# PCIE_USB.net
KiCad netlist of a schematic drawn in Altium Designer
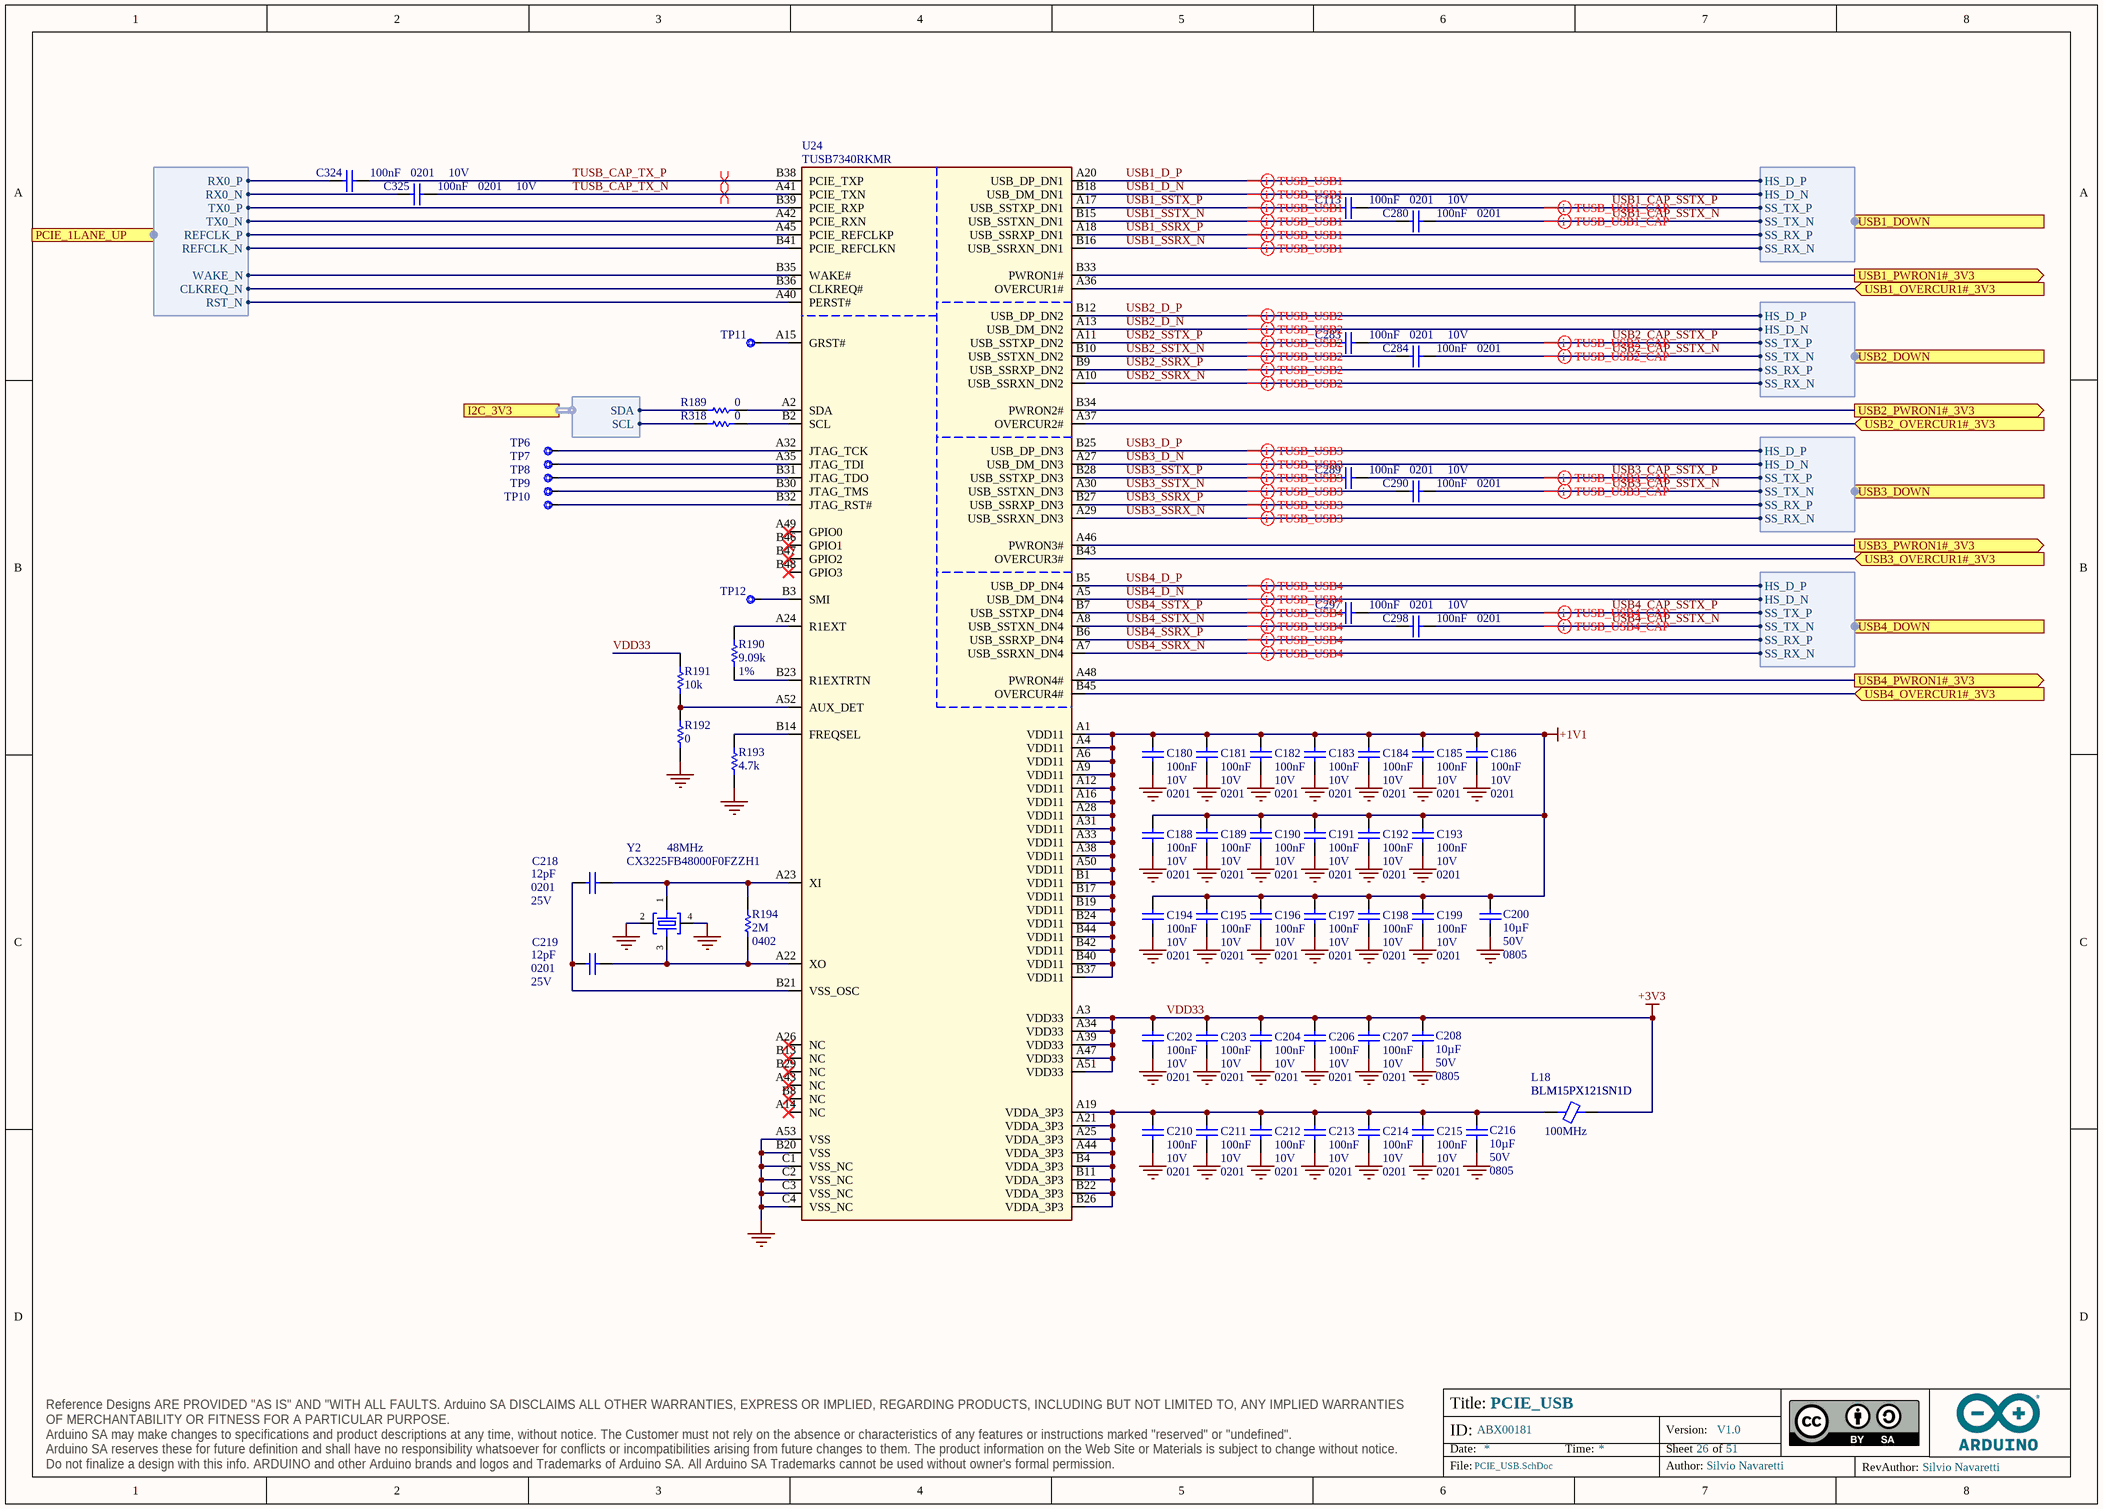
[diagram p0: PCIE_USB.SchDoc]

(export (version "E")
  (design (tool "Eeschema 10.0.6"))
  (components
    (comp (ref "C113")
      (value "100nF")
      (footprint "CAP-0201")
      (description "CAP CHIP 0201 100nF 10% 10V X5R")
      (fields
        (field (name "CASE CODE (IMPERIAL)") "0201")
        (field (name "TOLERANCE") "10%")
        (field (name "PART NUMBER") "CL03A104KP3NNNC")
        (field (name "VOLTAGE") "10V")
      )
      (libsource (lib "Clean") (part "CAP"))
    )
    (comp (ref "C180")
      (value "100nF")
      (footprint "CAP-0201")
      (description "CAP CHIP 0201 100nF 10% 10V X5R")
      (fields
        (field (name "PART NUMBER") "CL03A104KP3NNNC")
        (field (name "MANUFACTURER") "Samsung Electro-Mechanics")
        (field (name "VOLTAGE") "10V")
        (field (name "CASE CODE (IMPERIAL)") "0201")
      )
      (libsource (lib "Clean") (part "CAP"))
    )
    (comp (ref "C181")
      (value "100nF")
      (footprint "CAP-0201")
      (description "CAP CHIP 0201 100nF 10% 10V X5R")
      (fields
        (field (name "PART NUMBER") "CL03A104KP3NNNC")
        (field (name "MANUFACTURER") "Samsung Electro-Mechanics")
        (field (name "VOLTAGE") "10V")
        (field (name "CASE CODE (IMPERIAL)") "0201")
      )
      (libsource (lib "Clean") (part "CAP"))
    )
    (comp (ref "C182")
      (value "100nF")
      (footprint "CAP-0201")
      (description "CAP CHIP 0201 100nF 10% 10V X5R")
      (fields
        (field (name "PART NUMBER") "CL03A104KP3NNNC")
        (field (name "MANUFACTURER") "Samsung Electro-Mechanics")
        (field (name "VOLTAGE") "10V")
        (field (name "CASE CODE (IMPERIAL)") "0201")
      )
      (libsource (lib "Clean") (part "CAP"))
    )
    (comp (ref "C183")
      (value "100nF")
      (footprint "CAP-0201")
      (description "CAP CHIP 0201 100nF 10% 10V X5R")
      (fields
        (field (name "PART NUMBER") "CL03A104KP3NNNC")
        (field (name "MANUFACTURER") "Samsung Electro-Mechanics")
        (field (name "VOLTAGE") "10V")
        (field (name "CASE CODE (IMPERIAL)") "0201")
      )
      (libsource (lib "Clean") (part "CAP"))
    )
    (comp (ref "C184")
      (value "100nF")
      (footprint "CAP-0201")
      (description "CAP CHIP 0201 100nF 10% 10V X5R")
      (fields
        (field (name "PART NUMBER") "CL03A104KP3NNNC")
        (field (name "MANUFACTURER") "Samsung Electro-Mechanics")
        (field (name "VOLTAGE") "10V")
        (field (name "CASE CODE (IMPERIAL)") "0201")
      )
      (libsource (lib "Clean") (part "CAP"))
    )
    (comp (ref "C185")
      (value "100nF")
      (footprint "CAP-0201")
      (description "CAP CHIP 0201 100nF 10% 10V X5R")
      (fields
        (field (name "PART NUMBER") "CL03A104KP3NNNC")
        (field (name "MANUFACTURER") "Samsung Electro-Mechanics")
        (field (name "VOLTAGE") "10V")
        (field (name "CASE CODE (IMPERIAL)") "0201")
      )
      (libsource (lib "Clean") (part "CAP"))
    )
    (comp (ref "C186")
      (value "100nF")
      (footprint "CAP-0201")
      (description "CAP CHIP 0201 100nF 10% 10V X5R")
      (fields
        (field (name "PART NUMBER") "CL03A104KP3NNNC")
        (field (name "MANUFACTURER") "Samsung Electro-Mechanics")
        (field (name "VOLTAGE") "10V")
        (field (name "CASE CODE (IMPERIAL)") "0201")
      )
      (libsource (lib "Clean") (part "CAP"))
    )
    (comp (ref "C188")
      (value "100nF")
      (footprint "CAP-0201")
      (description "CAP CHIP 0201 100nF 10% 10V X5R")
      (fields
        (field (name "PART NUMBER") "CL03A104KP3NNNC")
        (field (name "MANUFACTURER") "Samsung Electro-Mechanics")
        (field (name "VOLTAGE") "10V")
        (field (name "CASE CODE (IMPERIAL)") "0201")
      )
      (libsource (lib "Clean") (part "CAP"))
    )
    (comp (ref "C189")
      (value "100nF")
      (footprint "CAP-0201")
      (description "CAP CHIP 0201 100nF 10% 10V X5R")
      (fields
        (field (name "PART NUMBER") "CL03A104KP3NNNC")
        (field (name "MANUFACTURER") "Samsung Electro-Mechanics")
        (field (name "VOLTAGE") "10V")
        (field (name "CASE CODE (IMPERIAL)") "0201")
      )
      (libsource (lib "Clean") (part "CAP"))
    )
    (comp (ref "C190")
      (value "100nF")
      (footprint "CAP-0201")
      (description "CAP CHIP 0201 100nF 10% 10V X5R")
      (fields
        (field (name "PART NUMBER") "CL03A104KP3NNNC")
        (field (name "MANUFACTURER") "Samsung Electro-Mechanics")
        (field (name "VOLTAGE") "10V")
        (field (name "CASE CODE (IMPERIAL)") "0201")
      )
      (libsource (lib "Clean") (part "CAP"))
    )
    (comp (ref "C191")
      (value "100nF")
      (footprint "CAP-0201")
      (description "CAP CHIP 0201 100nF 10% 10V X5R")
      (fields
        (field (name "PART NUMBER") "CL03A104KP3NNNC")
        (field (name "MANUFACTURER") "Samsung Electro-Mechanics")
        (field (name "VOLTAGE") "10V")
        (field (name "CASE CODE (IMPERIAL)") "0201")
      )
      (libsource (lib "Clean") (part "CAP"))
    )
    (comp (ref "C192")
      (value "100nF")
      (footprint "CAP-0201")
      (description "CAP CHIP 0201 100nF 10% 10V X5R")
      (fields
        (field (name "PART NUMBER") "CL03A104KP3NNNC")
        (field (name "MANUFACTURER") "Samsung Electro-Mechanics")
        (field (name "VOLTAGE") "10V")
        (field (name "CASE CODE (IMPERIAL)") "0201")
      )
      (libsource (lib "Clean") (part "CAP"))
    )
    (comp (ref "C193")
      (value "100nF")
      (footprint "CAP-0201")
      (description "CAP CHIP 0201 100nF 10% 10V X5R")
      (fields
        (field (name "PART NUMBER") "CL03A104KP3NNNC")
        (field (name "MANUFACTURER") "Samsung Electro-Mechanics")
        (field (name "VOLTAGE") "10V")
        (field (name "CASE CODE (IMPERIAL)") "0201")
      )
      (libsource (lib "Clean") (part "CAP"))
    )
    (comp (ref "C194")
      (value "100nF")
      (footprint "CAP-0201")
      (description "CAP CHIP 0201 100nF 10% 10V X5R")
      (fields
        (field (name "PART NUMBER") "CL03A104KP3NNNC")
        (field (name "MANUFACTURER") "Samsung Electro-Mechanics")
        (field (name "VOLTAGE") "10V")
        (field (name "CASE CODE (IMPERIAL)") "0201")
      )
      (libsource (lib "Clean") (part "CAP"))
    )
    (comp (ref "C195")
      (value "100nF")
      (footprint "CAP-0201")
      (description "CAP CHIP 0201 100nF 10% 10V X5R")
      (fields
        (field (name "PART NUMBER") "CL03A104KP3NNNC")
        (field (name "MANUFACTURER") "Samsung Electro-Mechanics")
        (field (name "VOLTAGE") "10V")
        (field (name "CASE CODE (IMPERIAL)") "0201")
      )
      (libsource (lib "Clean") (part "CAP"))
    )
    (comp (ref "C196")
      (value "100nF")
      (footprint "CAP-0201")
      (description "CAP CHIP 0201 100nF 10% 10V X5R")
      (fields
        (field (name "PART NUMBER") "CL03A104KP3NNNC")
        (field (name "MANUFACTURER") "Samsung Electro-Mechanics")
        (field (name "VOLTAGE") "10V")
        (field (name "CASE CODE (IMPERIAL)") "0201")
      )
      (libsource (lib "Clean") (part "CAP"))
    )
    (comp (ref "C197")
      (value "100nF")
      (footprint "CAP-0201")
      (description "CAP CHIP 0201 100nF 10% 10V X5R")
      (fields
        (field (name "PART NUMBER") "CL03A104KP3NNNC")
        (field (name "MANUFACTURER") "Samsung Electro-Mechanics")
        (field (name "VOLTAGE") "10V")
        (field (name "CASE CODE (IMPERIAL)") "0201")
      )
      (libsource (lib "Clean") (part "CAP"))
    )
    (comp (ref "C198")
      (value "100nF")
      (footprint "CAP-0201")
      (description "CAP CHIP 0201 100nF 10% 10V X5R")
      (fields
        (field (name "PART NUMBER") "CL03A104KP3NNNC")
        (field (name "MANUFACTURER") "Samsung Electro-Mechanics")
        (field (name "VOLTAGE") "10V")
        (field (name "CASE CODE (IMPERIAL)") "0201")
      )
      (libsource (lib "Clean") (part "CAP"))
    )
    (comp (ref "C199")
      (value "100nF")
      (footprint "CAP-0201")
      (description "CAP CHIP 0201 100nF 10% 10V X5R")
      (fields
        (field (name "PART NUMBER") "CL03A104KP3NNNC")
        (field (name "MANUFACTURER") "Samsung Electro-Mechanics")
        (field (name "VOLTAGE") "10V")
        (field (name "CASE CODE (IMPERIAL)") "0201")
      )
      (libsource (lib "Clean") (part "CAP"))
    )
    (comp (ref "C200")
      (value "10µF")
      (footprint "CAP-0805")
      (description "CAP CHIP 0805 10uF 20% 50V X5R")
      (fields
        (field (name "VOLTAGE") "50V")
        (field (name "PART NUMBER") "GRM21BR61H106ME43L")
        (field (name "CASE CODE (IMPERIAL)") "0805")
        (field (name "MANUFACTURER") "Murata Electronics")
      )
      (libsource (lib "Clean") (part "CAP"))
    )
    (comp (ref "C202")
      (value "100nF")
      (footprint "CAP-0201")
      (description "CAP CHIP 0201 100nF 10% 10V X5R")
      (fields
        (field (name "PART NUMBER") "CL03A104KP3NNNC")
        (field (name "MANUFACTURER") "Samsung Electro-Mechanics")
        (field (name "VOLTAGE") "10V")
        (field (name "CASE CODE (IMPERIAL)") "0201")
      )
      (libsource (lib "Clean") (part "CAP"))
    )
    (comp (ref "C203")
      (value "100nF")
      (footprint "CAP-0201")
      (description "CAP CHIP 0201 100nF 10% 10V X5R")
      (fields
        (field (name "PART NUMBER") "CL03A104KP3NNNC")
        (field (name "MANUFACTURER") "Samsung Electro-Mechanics")
        (field (name "VOLTAGE") "10V")
        (field (name "CASE CODE (IMPERIAL)") "0201")
      )
      (libsource (lib "Clean") (part "CAP"))
    )
    (comp (ref "C204")
      (value "100nF")
      (footprint "CAP-0201")
      (description "CAP CHIP 0201 100nF 10% 10V X5R")
      (fields
        (field (name "PART NUMBER") "CL03A104KP3NNNC")
        (field (name "MANUFACTURER") "Samsung Electro-Mechanics")
        (field (name "VOLTAGE") "10V")
        (field (name "CASE CODE (IMPERIAL)") "0201")
      )
      (libsource (lib "Clean") (part "CAP"))
    )
    (comp (ref "C206")
      (value "100nF")
      (footprint "CAP-0201")
      (description "CAP CHIP 0201 100nF 10% 10V X5R")
      (fields
        (field (name "PART NUMBER") "CL03A104KP3NNNC")
        (field (name "MANUFACTURER") "Samsung Electro-Mechanics")
        (field (name "VOLTAGE") "10V")
        (field (name "CASE CODE (IMPERIAL)") "0201")
      )
      (libsource (lib "Clean") (part "CAP"))
    )
    (comp (ref "C207")
      (value "100nF")
      (footprint "CAP-0201")
      (description "CAP CHIP 0201 100nF 10% 10V X5R")
      (fields
        (field (name "PART NUMBER") "CL03A104KP3NNNC")
        (field (name "MANUFACTURER") "Samsung Electro-Mechanics")
        (field (name "VOLTAGE") "10V")
        (field (name "CASE CODE (IMPERIAL)") "0201")
      )
      (libsource (lib "Clean") (part "CAP"))
    )
    (comp (ref "C208")
      (value "10µF")
      (footprint "CAP-0805")
      (description "CAP CHIP 0805 10uF 20% 50V X5R")
      (fields
        (field (name "VOLTAGE") "50V")
        (field (name "PART NUMBER") "GRM21BR61H106ME43L")
        (field (name "CASE CODE (IMPERIAL)") "0805")
        (field (name "MANUFACTURER") "Murata Electronics")
      )
      (libsource (lib "Clean") (part "CAP"))
    )
    (comp (ref "C210")
      (value "100nF")
      (footprint "CAP-0201")
      (description "CAP CHIP 0201 100nF 10% 10V X5R")
      (fields
        (field (name "PART NUMBER") "CL03A104KP3NNNC")
        (field (name "MANUFACTURER") "Samsung Electro-Mechanics")
        (field (name "VOLTAGE") "10V")
        (field (name "CASE CODE (IMPERIAL)") "0201")
      )
      (libsource (lib "Clean") (part "CAP"))
    )
    (comp (ref "C211")
      (value "100nF")
      (footprint "CAP-0201")
      (description "CAP CHIP 0201 100nF 10% 10V X5R")
      (fields
        (field (name "PART NUMBER") "CL03A104KP3NNNC")
        (field (name "MANUFACTURER") "Samsung Electro-Mechanics")
        (field (name "VOLTAGE") "10V")
        (field (name "CASE CODE (IMPERIAL)") "0201")
      )
      (libsource (lib "Clean") (part "CAP"))
    )
    (comp (ref "C212")
      (value "100nF")
      (footprint "CAP-0201")
      (description "CAP CHIP 0201 100nF 10% 10V X5R")
      (fields
        (field (name "PART NUMBER") "CL03A104KP3NNNC")
        (field (name "MANUFACTURER") "Samsung Electro-Mechanics")
        (field (name "VOLTAGE") "10V")
        (field (name "CASE CODE (IMPERIAL)") "0201")
      )
      (libsource (lib "Clean") (part "CAP"))
    )
    (comp (ref "C213")
      (value "100nF")
      (footprint "CAP-0201")
      (description "CAP CHIP 0201 100nF 10% 10V X5R")
      (fields
        (field (name "PART NUMBER") "CL03A104KP3NNNC")
        (field (name "MANUFACTURER") "Samsung Electro-Mechanics")
        (field (name "VOLTAGE") "10V")
        (field (name "CASE CODE (IMPERIAL)") "0201")
      )
      (libsource (lib "Clean") (part "CAP"))
    )
    (comp (ref "C214")
      (value "100nF")
      (footprint "CAP-0201")
      (description "CAP CHIP 0201 100nF 10% 10V X5R")
      (fields
        (field (name "PART NUMBER") "CL03A104KP3NNNC")
        (field (name "MANUFACTURER") "Samsung Electro-Mechanics")
        (field (name "VOLTAGE") "10V")
        (field (name "CASE CODE (IMPERIAL)") "0201")
      )
      (libsource (lib "Clean") (part "CAP"))
    )
    (comp (ref "C215")
      (value "100nF")
      (footprint "CAP-0201")
      (description "CAP CHIP 0201 100nF 10% 10V X5R")
      (fields
        (field (name "PART NUMBER") "CL03A104KP3NNNC")
        (field (name "MANUFACTURER") "Samsung Electro-Mechanics")
        (field (name "VOLTAGE") "10V")
        (field (name "CASE CODE (IMPERIAL)") "0201")
      )
      (libsource (lib "Clean") (part "CAP"))
    )
    (comp (ref "C216")
      (value "10µF")
      (footprint "CAP-0805")
      (description "CAP CHIP 0805 10uF 20% 50V X5R")
      (fields
        (field (name "VOLTAGE") "50V")
        (field (name "PART NUMBER") "GRM21BR61H106ME43L")
        (field (name "CASE CODE (IMPERIAL)") "0805")
        (field (name "MANUFACTURER") "Murata Electronics")
      )
      (libsource (lib "Clean") (part "CAP"))
    )
    (comp (ref "C218")
      (value "12pF")
      (footprint "CAP-0201")
      (description "CAP CHIP 0201 12pF 5% 25V C0G")
      (fields
        (field (name "CASE CODE (IMPERIAL)") "0201")
        (field (name "PART NUMBER") "GRM0335C1E120JA01J")
        (field (name "VOLTAGE") "25V")
        (field (name "TOLERANCE") "5%")
      )
      (libsource (lib "Clean") (part "CAP"))
    )
    (comp (ref "C219")
      (value "12pF")
      (footprint "CAP-0201")
      (description "CAP CHIP 0201 12pF 5% 25V C0G")
      (fields
        (field (name "CASE CODE (IMPERIAL)") "0201")
        (field (name "PART NUMBER") "GRM0335C1E120JA01J")
        (field (name "VOLTAGE") "25V")
        (field (name "TOLERANCE") "5%")
      )
      (libsource (lib "Clean") (part "CAP"))
    )
    (comp (ref "C280")
      (value "100nF")
      (footprint "CAP-0201")
      (description "CAP CHIP 0201 100nF 10% 10V X5R")
      (fields
        (field (name "CASE CODE (IMPERIAL)") "0201")
        (field (name "TOLERANCE") "10%")
        (field (name "PART NUMBER") "CL03A104KP3NNNC")
      )
      (libsource (lib "Clean") (part "CAP"))
    )
    (comp (ref "C283")
      (value "100nF")
      (footprint "CAP-0201")
      (description "CAP CHIP 0201 100nF 10% 10V X5R")
      (fields
        (field (name "CASE CODE (IMPERIAL)") "0201")
        (field (name "TOLERANCE") "10%")
        (field (name "PART NUMBER") "CL03A104KP3NNNC")
        (field (name "VOLTAGE") "10V")
      )
      (libsource (lib "Clean") (part "CAP"))
    )
    (comp (ref "C284")
      (value "100nF")
      (footprint "CAP-0201")
      (description "CAP CHIP 0201 100nF 10% 10V X5R")
      (fields
        (field (name "CASE CODE (IMPERIAL)") "0201")
        (field (name "TOLERANCE") "10%")
        (field (name "PART NUMBER") "CL03A104KP3NNNC")
      )
      (libsource (lib "Clean") (part "CAP"))
    )
    (comp (ref "C289")
      (value "100nF")
      (footprint "CAP-0201")
      (description "CAP CHIP 0201 100nF 10% 10V X5R")
      (fields
        (field (name "CASE CODE (IMPERIAL)") "0201")
        (field (name "TOLERANCE") "10%")
        (field (name "PART NUMBER") "CL03A104KP3NNNC")
        (field (name "VOLTAGE") "10V")
      )
      (libsource (lib "Clean") (part "CAP"))
    )
    (comp (ref "C290")
      (value "100nF")
      (footprint "CAP-0201")
      (description "CAP CHIP 0201 100nF 10% 10V X5R")
      (fields
        (field (name "CASE CODE (IMPERIAL)") "0201")
        (field (name "TOLERANCE") "10%")
        (field (name "PART NUMBER") "CL03A104KP3NNNC")
      )
      (libsource (lib "Clean") (part "CAP"))
    )
    (comp (ref "C297")
      (value "100nF")
      (footprint "CAP-0201")
      (description "CAP CHIP 0201 100nF 10% 10V X5R")
      (fields
        (field (name "CASE CODE (IMPERIAL)") "0201")
        (field (name "TOLERANCE") "10%")
        (field (name "PART NUMBER") "CL03A104KP3NNNC")
        (field (name "VOLTAGE") "10V")
      )
      (libsource (lib "Clean") (part "CAP"))
    )
    (comp (ref "C298")
      (value "100nF")
      (footprint "CAP-0201")
      (description "CAP CHIP 0201 100nF 10% 10V X5R")
      (fields
        (field (name "CASE CODE (IMPERIAL)") "0201")
        (field (name "TOLERANCE") "10%")
        (field (name "PART NUMBER") "CL03A104KP3NNNC")
      )
      (libsource (lib "Clean") (part "CAP"))
    )
    (comp (ref "C324")
      (value "100nF")
      (footprint "CAP-0201")
      (description "CAP CHIP 0201 100nF 10% 10V X5R")
      (fields
        (field (name "CASE CODE (IMPERIAL)") "0201")
        (field (name "TOLERANCE") "10%")
        (field (name "PART NUMBER") "CL03A104KP3NNNC")
        (field (name "VOLTAGE") "10V")
      )
      (libsource (lib "Clean") (part "CAP"))
    )
    (comp (ref "C325")
      (value "100nF")
      (footprint "CAP-0201")
      (description "CAP CHIP 0201 100nF 10% 10V X5R")
      (fields
        (field (name "CASE CODE (IMPERIAL)") "0201")
        (field (name "TOLERANCE") "10%")
        (field (name "PART NUMBER") "CL03A104KP3NNNC")
        (field (name "VOLTAGE") "10V")
      )
      (libsource (lib "Clean") (part "CAP"))
    )
    (comp (ref "L18")
      (value "BLM15PX121SN1D")
      (footprint "L-0402")
      (description "FERRITE SMD 0402 120Ohm 25% 100MHz Ferrite 2A")
      (fields
        (field (name "PART NUMBER") "BLM15PX121SN1D")
        (field (name "TEST FREQUENCY") "100MHz")
        (field (name "MANUFACTURER") "Murata")
        (field (name "TOLERANCE") "25%")
      )
      (libsource (lib "Clean") (part "Ferrite"))
    )
    (comp (ref "R189")
      (value "0")
      (footprint "RES-0201")
      (description "RES CHIP 0201 0R")
      (fields (field (name "MANUFACTURER") "Vishay") (field (name "PART NUMBER") "CRCW02010000Z0ED"))
      (libsource (lib "Clean") (part "RES"))
    )
    (comp (ref "R190")
      (value "9.09k")
      (footprint "RES-0201")
      (description "RES CHIP 0201 9k09 1% 1/20W")
      (fields
        (field (name "MANUFACTURER") "YAGEO")
        (field (name "PART NUMBER") "RC0201FR-079K09L")
        (field (name "TOLERANCE") "1%")
      )
      (libsource (lib "Clean") (part "RES"))
    )
    (comp (ref "R191")
      (value "10k")
      (footprint "RES-0201")
      (description "RES CHIP 0201 10k 1% 1/20W")
      (fields (field (name "POWER") "50mW") (field (name "TOLERANCE") "1%"))
      (libsource (lib "Clean") (part "RES"))
    )
    (comp (ref "R192")
      (value "0")
      (footprint "RES-0201")
      (description "RES CHIP 0201 0R")
      (fields (field (name "MANUFACTURER") "Vishay") (field (name "PART NUMBER") "CRCW02010000Z0ED"))
      (libsource (lib "Clean") (part "RES"))
    )
    (comp (ref "R193")
      (value "4.7k")
      (footprint "RES-0201")
      (description "RES CHIP 0201 4k7 1% 1/20W")
      (fields (field (name "POWER") "50mW") (field (name "PART NUMBER") "RC0201FR-074K7L"))
      (libsource (lib "Clean") (part "RES"))
    )
    (comp (ref "R194")
      (value "2M")
      (footprint "RES-0402")
      (description "RES CHIP 0402 2M 1% 1/16W")
      (fields
        (field (name "PART NUMBER") "RC0402FR-072ML")
        (field (name "CASE CODE (IMPERIAL)") "0402")
        (field (name "MANUFACTURER") "YAGEO")
      )
      (libsource (lib "Clean") (part "RES"))
    )
    (comp (ref "R318")
      (value "0")
      (footprint "RES-0201")
      (description "RES CHIP 0201 0R")
      (fields (field (name "MANUFACTURER") "Vishay") (field (name "PART NUMBER") "CRCW02010000Z0ED"))
      (libsource (lib "Clean") (part "RES"))
    )
    (comp (ref "TP6")
      (value "Test point 1.00mm")
      (footprint "TP-1.00MM")
      (fields (field (name "PART NUMBER") "This is not a component"))
      (libsource (lib "Clean") (part "TESTPOINT"))
    )
    (comp (ref "TP7")
      (value "Test point 1.00mm")
      (footprint "TP-1.00MM")
      (fields (field (name "PART NUMBER") "This is not a component"))
      (libsource (lib "Clean") (part "TESTPOINT"))
    )
    (comp (ref "TP8")
      (value "Test point 1.00mm")
      (footprint "TP-1.00MM")
      (fields (field (name "PART NUMBER") "This is not a component"))
      (libsource (lib "Clean") (part "TESTPOINT"))
    )
    (comp (ref "TP9")
      (value "Test point 1.00mm")
      (footprint "TP-1.00MM")
      (fields (field (name "PART NUMBER") "This is not a component"))
      (libsource (lib "Clean") (part "TESTPOINT"))
    )
    (comp (ref "TP10")
      (value "Test point 1.00mm")
      (footprint "TP-1.00MM")
      (fields (field (name "PART NUMBER") "This is not a component"))
      (libsource (lib "Clean") (part "TESTPOINT"))
    )
    (comp (ref "TP11")
      (value "Test point 1.00mm")
      (footprint "TP-1.00MM")
      (fields (field (name "PART NUMBER") "This is not a component"))
      (libsource (lib "Clean") (part "TESTPOINT"))
    )
    (comp (ref "TP12")
      (value "Test point 1.00mm")
      (footprint "TP-1.00MM")
      (fields (field (name "PART NUMBER") "This is not a component"))
      (libsource (lib "Clean") (part "TESTPOINT"))
    )
    (comp (ref "U24")
      (value "TUSB7340RKMR")
      (footprint "TI RKM S-PWQFN-N100 Double row 9x9mm pitch 0.6mm")
      (description "IC PCIe x1 Gen2 to x4 USB 3.0 converter, QFN-MR100 9x9mm")
      (fields (field (name "MANUFACTURER") "Texas Instruments"))
      (libsource (lib "Clean") (part "TUSB7340RKMR-Symbol-1"))
    )
    (comp (ref "Y2")
      (value "CX3225FB48000F0FZZH1")
      (footprint "CRYSTAL3.2X2.5")
      (description "CRYSTAL 48MHz tolerance 10ppm stability 20ppm load 10pF 3.2x2.5mm")
      (fields (field (name "FREQUENCY") "48MHz") (field (name "MANUFACTURER") "Kyocera"))
      (libsource (lib "Clean") (part "Crystal"))
    )
  )
  (nets
    (net (code "4") (name "+1V1") (class "Default")
      (node (ref "C180") (pin "2") (pinfunction "2_2") (pintype "passive"))
      (node (ref "C181") (pin "2") (pinfunction "2_2") (pintype "passive"))
      (node (ref "C182") (pin "2") (pinfunction "2_2") (pintype "passive"))
      (node (ref "C183") (pin "2") (pinfunction "2_2") (pintype "passive"))
      (node (ref "C184") (pin "2") (pinfunction "2_2") (pintype "passive"))
      (node (ref "C185") (pin "2") (pinfunction "2_2") (pintype "passive"))
      (node (ref "C186") (pin "2") (pinfunction "2_2") (pintype "passive"))
      (node (ref "C188") (pin "2") (pinfunction "2_2") (pintype "passive"))
      (node (ref "C189") (pin "2") (pinfunction "2_2") (pintype "passive"))
      (node (ref "C190") (pin "2") (pinfunction "2_2") (pintype "passive"))
      (node (ref "C191") (pin "2") (pinfunction "2_2") (pintype "passive"))
      (node (ref "C192") (pin "2") (pinfunction "2_2") (pintype "passive"))
      (node (ref "C193") (pin "2") (pinfunction "2_2") (pintype "passive"))
      (node (ref "C194") (pin "2") (pinfunction "2_2") (pintype "passive"))
      (node (ref "C195") (pin "2") (pinfunction "2_2") (pintype "passive"))
      (node (ref "C196") (pin "2") (pinfunction "2_2") (pintype "passive"))
      (node (ref "C197") (pin "2") (pinfunction "2_2") (pintype "passive"))
      (node (ref "C198") (pin "2") (pinfunction "2_2") (pintype "passive"))
      (node (ref "C199") (pin "2") (pinfunction "2_2") (pintype "passive"))
      (node (ref "C200") (pin "2") (pinfunction "2_2") (pintype "passive"))
      (node (ref "U24") (pin "A1") (pinfunction "VDD11_A1") (pintype "passive"))
      (node (ref "U24") (pin "A12") (pinfunction "VDD11_A12") (pintype "passive"))
      (node (ref "U24") (pin "A16") (pinfunction "VDD11_A16") (pintype "passive"))
      (node (ref "U24") (pin "A28") (pinfunction "VDD11_A28") (pintype "passive"))
      (node (ref "U24") (pin "A31") (pinfunction "VDD11_A31") (pintype "passive"))
      (node (ref "U24") (pin "A33") (pinfunction "VDD11_A33") (pintype "passive"))
      (node (ref "U24") (pin "A38") (pinfunction "VDD11_A38") (pintype "passive"))
      (node (ref "U24") (pin "A4") (pinfunction "VDD11_A4") (pintype "passive"))
      (node (ref "U24") (pin "A50") (pinfunction "VDD11_A50") (pintype "passive"))
      (node (ref "U24") (pin "A6") (pinfunction "VDD11_A6") (pintype "passive"))
      (node (ref "U24") (pin "A9") (pinfunction "VDD11_A9") (pintype "passive"))
      (node (ref "U24") (pin "B1") (pinfunction "VDD11_B1") (pintype "passive"))
      (node (ref "U24") (pin "B17") (pinfunction "VDD11_B17") (pintype "passive"))
      (node (ref "U24") (pin "B19") (pinfunction "VDD11_B19") (pintype "passive"))
      (node (ref "U24") (pin "B24") (pinfunction "VDD11_B24") (pintype "passive"))
      (node (ref "U24") (pin "B37") (pinfunction "VDD11_B37") (pintype "passive"))
      (node (ref "U24") (pin "B40") (pinfunction "VDD11_B40") (pintype "passive"))
      (node (ref "U24") (pin "B42") (pinfunction "VDD11_B42") (pintype "passive"))
      (node (ref "U24") (pin "B44") (pinfunction "VDD11_B44") (pintype "passive"))
    )
    (net (code "5") (name "+3V3") (class "Default")
      (node (ref "C202") (pin "2") (pinfunction "2_2") (pintype "passive"))
      (node (ref "C203") (pin "2") (pinfunction "2_2") (pintype "passive"))
      (node (ref "C204") (pin "2") (pinfunction "2_2") (pintype "passive"))
      (node (ref "C206") (pin "2") (pinfunction "2_2") (pintype "passive"))
      (node (ref "C207") (pin "2") (pinfunction "2_2") (pintype "passive"))
      (node (ref "C208") (pin "2") (pinfunction "2_2") (pintype "passive"))
      (node (ref "L18") (pin "2") (pinfunction "2_2") (pintype "passive"))
      (node (ref "R191") (pin "2") (pinfunction "2_2") (pintype "passive"))
      (node (ref "U24") (pin "A3") (pinfunction "VDD33_A3") (pintype "passive"))
      (node (ref "U24") (pin "A34") (pinfunction "VDD33_A34") (pintype "passive"))
      (node (ref "U24") (pin "A39") (pinfunction "VDD33_A39") (pintype "passive"))
      (node (ref "U24") (pin "A47") (pinfunction "VDD33_A47") (pintype "passive"))
      (node (ref "U24") (pin "A51") (pinfunction "VDD33_A51") (pintype "passive"))
    )
    (net (code "6") (name "/CLKREQ_N") (class "Default")
      (node (ref "U24") (pin "B36") (pinfunction "CLKREQ#_B36") (pintype "passive"))
    )
    (net (code "7") (name "/REFCLK_N") (class "Default")
      (node (ref "U24") (pin "B41") (pinfunction "PCIE_REFCLKN_B41") (pintype "passive"))
    )
    (net (code "8") (name "/REFCLK_P") (class "Default")
      (node (ref "U24") (pin "A45") (pinfunction "PCIE_REFCLKP_A45") (pintype "passive"))
    )
    (net (code "9") (name "/RST_N") (class "Default")
      (node (ref "U24") (pin "A40") (pinfunction "PERST#_A40") (pintype "passive"))
    )
    (net (code "10") (name "/RX0_N") (class "Default")
      (node (ref "C325") (pin "1") (pinfunction "1_1") (pintype "passive"))
    )
    (net (code "11") (name "/RX0_P") (class "Default")
      (node (ref "C324") (pin "1") (pinfunction "1_1") (pintype "passive"))
    )
    (net (code "12") (name "/SCL") (class "Default")
      (node (ref "R318") (pin "1") (pinfunction "1_1") (pintype "passive"))
    )
    (net (code "13") (name "/SDA") (class "Default")
      (node (ref "R189") (pin "1") (pinfunction "1_1") (pintype "passive"))
    )
    (net (code "14") (name "/TUSB_CAP_TX_N") (class "Default")
      (node (ref "C325") (pin "2") (pinfunction "2_2") (pintype "passive"))
      (node (ref "U24") (pin "A41") (pinfunction "PCIE_TXN_A41") (pintype "passive"))
    )
    (net (code "15") (name "/TUSB_CAP_TX_P") (class "Default")
      (node (ref "C324") (pin "2") (pinfunction "2_2") (pintype "passive"))
      (node (ref "U24") (pin "B38") (pinfunction "PCIE_TXP_B38") (pintype "passive"))
    )
    (net (code "16") (name "/TX0_N") (class "Default")
      (node (ref "U24") (pin "A42") (pinfunction "PCIE_RXN_A42") (pintype "passive"))
    )
    (net (code "17") (name "/TX0_P") (class "Default")
      (node (ref "U24") (pin "B39") (pinfunction "PCIE_RXP_B39") (pintype "passive"))
    )
    (net (code "18") (name "/USB1_CAP_SSTX_N") (class "Default")
      (node (ref "C280") (pin "2") (pinfunction "2_2") (pintype "passive"))
    )
    (net (code "19") (name "/USB1_CAP_SSTX_P") (class "Default")
      (node (ref "C113") (pin "2") (pinfunction "2_2") (pintype "passive"))
    )
    (net (code "20") (name "/USB1_D_N") (class "Default")
      (node (ref "U24") (pin "B18") (pinfunction "USB_DM_DN1_B18") (pintype "passive"))
    )
    (net (code "21") (name "/USB1_D_P") (class "Default")
      (node (ref "U24") (pin "A20") (pinfunction "USB_DP_DN1_A20") (pintype "passive"))
    )
    (net (code "22") (name "/USB1_OVERCUR1#_3V3") (class "Default")
      (node (ref "U24") (pin "A36") (pinfunction "OVERCUR1#_A36") (pintype "passive"))
    )
    (net (code "23") (name "/USB1_PWRON1#_3V3") (class "Default")
      (node (ref "U24") (pin "B33") (pinfunction "PWRON1#_B33") (pintype "passive"))
    )
    (net (code "24") (name "/USB1_SSRX_N") (class "Default")
      (node (ref "U24") (pin "B16") (pinfunction "USB_SSRXN_DN1_B16") (pintype "passive"))
    )
    (net (code "25") (name "/USB1_SSRX_P") (class "Default")
      (node (ref "U24") (pin "A18") (pinfunction "USB_SSRXP_DN1_A18") (pintype "passive"))
    )
    (net (code "26") (name "/USB1_SSTX_N") (class "Default")
      (node (ref "C280") (pin "1") (pinfunction "1_1") (pintype "passive"))
      (node (ref "U24") (pin "B15") (pinfunction "USB_SSTXN_DN1_B15") (pintype "passive"))
    )
    (net (code "27") (name "/USB1_SSTX_P") (class "Default")
      (node (ref "C113") (pin "1") (pinfunction "1_1") (pintype "passive"))
      (node (ref "U24") (pin "A17") (pinfunction "USB_SSTXP_DN1_A17") (pintype "passive"))
    )
    (net (code "28") (name "/USB2_CAP_SSTX_N") (class "Default")
      (node (ref "C284") (pin "2") (pinfunction "2_2") (pintype "passive"))
    )
    (net (code "29") (name "/USB2_CAP_SSTX_P") (class "Default")
      (node (ref "C283") (pin "2") (pinfunction "2_2") (pintype "passive"))
    )
    (net (code "30") (name "/USB2_D_N") (class "Default")
      (node (ref "U24") (pin "A13") (pinfunction "USB_DM_DN2_A13") (pintype "passive"))
    )
    (net (code "31") (name "/USB2_D_P") (class "Default")
      (node (ref "U24") (pin "B12") (pinfunction "USB_DP_DN2_B12") (pintype "passive"))
    )
    (net (code "32") (name "/USB2_OVERCUR1#_3V3") (class "Default")
      (node (ref "U24") (pin "A37") (pinfunction "OVERCUR2#_A37") (pintype "passive"))
    )
    (net (code "33") (name "/USB2_PWRON1#_3V3") (class "Default")
      (node (ref "U24") (pin "B34") (pinfunction "PWRON2#_B34") (pintype "passive"))
    )
    (net (code "34") (name "/USB2_SSRX_N") (class "Default")
      (node (ref "U24") (pin "A10") (pinfunction "USB_SSRXN_DN2_A10") (pintype "passive"))
    )
    (net (code "35") (name "/USB2_SSRX_P") (class "Default")
      (node (ref "U24") (pin "B9") (pinfunction "USB_SSRXP_DN2_B9") (pintype "passive"))
    )
    (net (code "36") (name "/USB2_SSTX_N") (class "Default")
      (node (ref "C284") (pin "1") (pinfunction "1_1") (pintype "passive"))
      (node (ref "U24") (pin "B10") (pinfunction "USB_SSTXN_DN2_B10") (pintype "passive"))
    )
    (net (code "37") (name "/USB2_SSTX_P") (class "Default")
      (node (ref "C283") (pin "1") (pinfunction "1_1") (pintype "passive"))
      (node (ref "U24") (pin "A11") (pinfunction "USB_SSTXP_DN2_A11") (pintype "passive"))
    )
    (net (code "38") (name "/USB3_CAP_SSTX_N") (class "Default")
      (node (ref "C290") (pin "2") (pinfunction "2_2") (pintype "passive"))
    )
    (net (code "39") (name "/USB3_CAP_SSTX_P") (class "Default")
      (node (ref "C289") (pin "2") (pinfunction "2_2") (pintype "passive"))
    )
    (net (code "40") (name "/USB3_D_N") (class "Default")
      (node (ref "U24") (pin "A27") (pinfunction "USB_DM_DN3_A27") (pintype "passive"))
    )
    (net (code "41") (name "/USB3_D_P") (class "Default")
      (node (ref "U24") (pin "B25") (pinfunction "USB_DP_DN3_B25") (pintype "passive"))
    )
    (net (code "42") (name "/USB3_OVERCUR1#_3V3") (class "Default")
      (node (ref "U24") (pin "B43") (pinfunction "OVERCUR3#_B43") (pintype "passive"))
    )
    (net (code "43") (name "/USB3_PWRON1#_3V3") (class "Default")
      (node (ref "U24") (pin "A46") (pinfunction "PWRON3#_A46") (pintype "passive"))
    )
    (net (code "44") (name "/USB3_SSRX_N") (class "Default")
      (node (ref "U24") (pin "A29") (pinfunction "USB_SSRXN_DN3_A29") (pintype "passive"))
    )
    (net (code "45") (name "/USB3_SSRX_P") (class "Default")
      (node (ref "U24") (pin "B27") (pinfunction "USB_SSRXP_DN3_B27") (pintype "passive"))
    )
    (net (code "46") (name "/USB3_SSTX_N") (class "Default")
      (node (ref "C290") (pin "1") (pinfunction "1_1") (pintype "passive"))
      (node (ref "U24") (pin "A30") (pinfunction "USB_SSTXN_DN3_A30") (pintype "passive"))
    )
    (net (code "47") (name "/USB3_SSTX_P") (class "Default")
      (node (ref "C289") (pin "1") (pinfunction "1_1") (pintype "passive"))
      (node (ref "U24") (pin "B28") (pinfunction "USB_SSTXP_DN3_B28") (pintype "passive"))
    )
    (net (code "48") (name "/USB4_CAP_SSTX_N") (class "Default")
      (node (ref "C298") (pin "2") (pinfunction "2_2") (pintype "passive"))
    )
    (net (code "49") (name "/USB4_CAP_SSTX_P") (class "Default")
      (node (ref "C297") (pin "2") (pinfunction "2_2") (pintype "passive"))
    )
    (net (code "50") (name "/USB4_D_N") (class "Default")
      (node (ref "U24") (pin "A5") (pinfunction "USB_DM_DN4_A5") (pintype "passive"))
    )
    (net (code "51") (name "/USB4_D_P") (class "Default")
      (node (ref "U24") (pin "B5") (pinfunction "USB_DP_DN4_B5") (pintype "passive"))
    )
    (net (code "52") (name "/USB4_OVERCUR1#_3V3") (class "Default")
      (node (ref "U24") (pin "B45") (pinfunction "OVERCUR4#_B45") (pintype "passive"))
    )
    (net (code "53") (name "/USB4_PWRON1#_3V3") (class "Default")
      (node (ref "U24") (pin "A48") (pinfunction "PWRON4#_A48") (pintype "passive"))
    )
    (net (code "54") (name "/USB4_SSRX_N") (class "Default")
      (node (ref "U24") (pin "A7") (pinfunction "USB_SSRXN_DN4_A7") (pintype "passive"))
    )
    (net (code "55") (name "/USB4_SSRX_P") (class "Default")
      (node (ref "U24") (pin "B6") (pinfunction "USB_SSRXP_DN4_B6") (pintype "passive"))
    )
    (net (code "56") (name "/USB4_SSTX_N") (class "Default")
      (node (ref "C298") (pin "1") (pinfunction "1_1") (pintype "passive"))
      (node (ref "U24") (pin "A8") (pinfunction "USB_SSTXN_DN4_A8") (pintype "passive"))
    )
    (net (code "57") (name "/USB4_SSTX_P") (class "Default")
      (node (ref "C297") (pin "1") (pinfunction "1_1") (pintype "passive"))
      (node (ref "U24") (pin "B7") (pinfunction "USB_SSTXP_DN4_B7") (pintype "passive"))
    )
    (net (code "58") (name "/WAKE_N") (class "Default")
      (node (ref "U24") (pin "B35") (pinfunction "WAKE#_B35") (pintype "passive"))
    )
    (net (code "62") (name "GND") (class "Default")
      (node (ref "C180") (pin "1") (pinfunction "1_1") (pintype "passive"))
      (node (ref "C181") (pin "1") (pinfunction "1_1") (pintype "passive"))
      (node (ref "C182") (pin "1") (pinfunction "1_1") (pintype "passive"))
      (node (ref "C183") (pin "1") (pinfunction "1_1") (pintype "passive"))
      (node (ref "C184") (pin "1") (pinfunction "1_1") (pintype "passive"))
      (node (ref "C185") (pin "1") (pinfunction "1_1") (pintype "passive"))
      (node (ref "C186") (pin "1") (pinfunction "1_1") (pintype "passive"))
      (node (ref "C188") (pin "1") (pinfunction "1_1") (pintype "passive"))
      (node (ref "C189") (pin "1") (pinfunction "1_1") (pintype "passive"))
      (node (ref "C190") (pin "1") (pinfunction "1_1") (pintype "passive"))
      (node (ref "C191") (pin "1") (pinfunction "1_1") (pintype "passive"))
      (node (ref "C192") (pin "1") (pinfunction "1_1") (pintype "passive"))
      (node (ref "C193") (pin "1") (pinfunction "1_1") (pintype "passive"))
      (node (ref "C194") (pin "1") (pinfunction "1_1") (pintype "passive"))
      (node (ref "C195") (pin "1") (pinfunction "1_1") (pintype "passive"))
      (node (ref "C196") (pin "1") (pinfunction "1_1") (pintype "passive"))
      (node (ref "C197") (pin "1") (pinfunction "1_1") (pintype "passive"))
      (node (ref "C198") (pin "1") (pinfunction "1_1") (pintype "passive"))
      (node (ref "C199") (pin "1") (pinfunction "1_1") (pintype "passive"))
      (node (ref "C200") (pin "1") (pinfunction "1_1") (pintype "passive"))
      (node (ref "C202") (pin "1") (pinfunction "1_1") (pintype "passive"))
      (node (ref "C203") (pin "1") (pinfunction "1_1") (pintype "passive"))
      (node (ref "C204") (pin "1") (pinfunction "1_1") (pintype "passive"))
      (node (ref "C206") (pin "1") (pinfunction "1_1") (pintype "passive"))
      (node (ref "C207") (pin "1") (pinfunction "1_1") (pintype "passive"))
      (node (ref "C208") (pin "1") (pinfunction "1_1") (pintype "passive"))
      (node (ref "C210") (pin "1") (pinfunction "1_1") (pintype "passive"))
      (node (ref "C211") (pin "1") (pinfunction "1_1") (pintype "passive"))
      (node (ref "C212") (pin "1") (pinfunction "1_1") (pintype "passive"))
      (node (ref "C213") (pin "1") (pinfunction "1_1") (pintype "passive"))
      (node (ref "C214") (pin "1") (pinfunction "1_1") (pintype "passive"))
      (node (ref "C215") (pin "1") (pinfunction "1_1") (pintype "passive"))
      (node (ref "C216") (pin "1") (pinfunction "1_1") (pintype "passive"))
      (node (ref "R192") (pin "2") (pinfunction "2_2") (pintype "passive"))
      (node (ref "R193") (pin "2") (pinfunction "2_2") (pintype "passive"))
      (node (ref "U24") (pin "A53") (pinfunction "VSS_A53") (pintype "passive"))
      (node (ref "U24") (pin "B20") (pinfunction "VSS_B20") (pintype "passive"))
      (node (ref "U24") (pin "C1") (pinfunction "VSS_NC_C1") (pintype "passive"))
      (node (ref "U24") (pin "C2") (pinfunction "VSS_NC_C2") (pintype "passive"))
      (node (ref "U24") (pin "C3") (pinfunction "VSS_NC_C3") (pintype "passive"))
      (node (ref "U24") (pin "C4") (pinfunction "VSS_NC_C4") (pintype "passive"))
      (node (ref "Y2") (pin "2") (pinfunction "2_2") (pintype "passive"))
      (node (ref "Y2") (pin "4") (pinfunction "4_4") (pintype "passive"))
    )
    (net (code "63") (name "Net-(C210-Pad2)") (class "Default")
      (node (ref "C210") (pin "2") (pinfunction "2_2") (pintype "passive"))
      (node (ref "C211") (pin "2") (pinfunction "2_2") (pintype "passive"))
      (node (ref "C212") (pin "2") (pinfunction "2_2") (pintype "passive"))
      (node (ref "C213") (pin "2") (pinfunction "2_2") (pintype "passive"))
      (node (ref "C214") (pin "2") (pinfunction "2_2") (pintype "passive"))
      (node (ref "C215") (pin "2") (pinfunction "2_2") (pintype "passive"))
      (node (ref "C216") (pin "2") (pinfunction "2_2") (pintype "passive"))
      (node (ref "L18") (pin "1") (pinfunction "1_1") (pintype "passive"))
      (node (ref "U24") (pin "A19") (pinfunction "VDDA_3P3_A19") (pintype "passive"))
      (node (ref "U24") (pin "A21") (pinfunction "VDDA_3P3_A21") (pintype "passive"))
      (node (ref "U24") (pin "A25") (pinfunction "VDDA_3P3_A25") (pintype "passive"))
      (node (ref "U24") (pin "A44") (pinfunction "VDDA_3P3_A44") (pintype "passive"))
      (node (ref "U24") (pin "B11") (pinfunction "VDDA_3P3_B11") (pintype "passive"))
      (node (ref "U24") (pin "B22") (pinfunction "VDDA_3P3_B22") (pintype "passive"))
      (node (ref "U24") (pin "B26") (pinfunction "VDDA_3P3_B26") (pintype "passive"))
      (node (ref "U24") (pin "B4") (pinfunction "VDDA_3P3_B4") (pintype "passive"))
    )
    (net (code "64") (name "Net-(U24-AUX_DET)") (class "Default")
      (node (ref "R191") (pin "1") (pinfunction "1_1") (pintype "passive"))
      (node (ref "R192") (pin "1") (pinfunction "1_1") (pintype "passive"))
      (node (ref "U24") (pin "A52") (pinfunction "AUX_DET_A52") (pintype "passive"))
    )
    (net (code "65") (name "Net-(U24-FREQSEL)") (class "Default")
      (node (ref "R193") (pin "1") (pinfunction "1_1") (pintype "passive"))
      (node (ref "U24") (pin "B14") (pinfunction "FREQSEL_B14") (pintype "passive"))
    )
    (net (code "66") (name "Net-(U24-GRST#)") (class "Default")
      (node (ref "TP11") (pin "X") (pinfunction "X_X") (pintype "passive"))
      (node (ref "U24") (pin "A15") (pinfunction "GRST#_A15") (pintype "passive"))
    )
    (net (code "67") (name "Net-(U24-JTAG_RST#)") (class "Default")
      (node (ref "TP10") (pin "X") (pinfunction "X_X") (pintype "passive"))
      (node (ref "U24") (pin "B32") (pinfunction "JTAG_RST#_B32") (pintype "passive"))
    )
    (net (code "68") (name "Net-(U24-JTAG_TCK)") (class "Default")
      (node (ref "TP6") (pin "X") (pinfunction "X_X") (pintype "passive"))
      (node (ref "U24") (pin "A32") (pinfunction "JTAG_TCK_A32") (pintype "passive"))
    )
    (net (code "69") (name "Net-(U24-JTAG_TDI)") (class "Default")
      (node (ref "TP7") (pin "X") (pinfunction "X_X") (pintype "passive"))
      (node (ref "U24") (pin "A35") (pinfunction "JTAG_TDI_A35") (pintype "passive"))
    )
    (net (code "70") (name "Net-(U24-JTAG_TDO)") (class "Default")
      (node (ref "TP8") (pin "X") (pinfunction "X_X") (pintype "passive"))
      (node (ref "U24") (pin "B31") (pinfunction "JTAG_TDO_B31") (pintype "passive"))
    )
    (net (code "71") (name "Net-(U24-JTAG_TMS)") (class "Default")
      (node (ref "TP9") (pin "X") (pinfunction "X_X") (pintype "passive"))
      (node (ref "U24") (pin "B30") (pinfunction "JTAG_TMS_B30") (pintype "passive"))
    )
    (net (code "72") (name "Net-(U24-R1EXT)") (class "Default")
      (node (ref "R190") (pin "1") (pinfunction "1_1") (pintype "passive"))
      (node (ref "U24") (pin "A24") (pinfunction "R1EXT_A24") (pintype "passive"))
    )
    (net (code "73") (name "Net-(U24-R1EXTRTN)") (class "Default")
      (node (ref "R190") (pin "2") (pinfunction "2_2") (pintype "passive"))
      (node (ref "U24") (pin "B23") (pinfunction "R1EXTRTN_B23") (pintype "passive"))
    )
    (net (code "74") (name "Net-(U24-SCL)") (class "Default")
      (node (ref "R318") (pin "2") (pinfunction "2_2") (pintype "passive"))
      (node (ref "U24") (pin "B2") (pinfunction "SCL_B2") (pintype "passive"))
    )
    (net (code "75") (name "Net-(U24-SDA)") (class "Default")
      (node (ref "R189") (pin "2") (pinfunction "2_2") (pintype "passive"))
      (node (ref "U24") (pin "A2") (pinfunction "SDA_A2") (pintype "passive"))
    )
    (net (code "76") (name "Net-(U24-SMI)") (class "Default")
      (node (ref "TP12") (pin "X") (pinfunction "X_X") (pintype "passive"))
      (node (ref "U24") (pin "B3") (pinfunction "SMI_B3") (pintype "passive"))
    )
    (net (code "77") (name "Net-(U24-VSS_OSC)") (class "Default")
      (node (ref "C218") (pin "2") (pinfunction "2_2") (pintype "passive"))
      (node (ref "C219") (pin "2") (pinfunction "2_2") (pintype "passive"))
      (node (ref "U24") (pin "B21") (pinfunction "VSS_OSC_B21") (pintype "passive"))
    )
    (net (code "78") (name "Net-(U24-XI)") (class "Default")
      (node (ref "C218") (pin "1") (pinfunction "1_1") (pintype "passive"))
      (node (ref "R194") (pin "2") (pinfunction "2_2") (pintype "passive"))
      (node (ref "U24") (pin "A23") (pinfunction "XI_A23") (pintype "passive"))
      (node (ref "Y2") (pin "1") (pinfunction "1_1") (pintype "passive"))
    )
    (net (code "79") (name "Net-(U24-XO)") (class "Default")
      (node (ref "C219") (pin "1") (pinfunction "1_1") (pintype "passive"))
      (node (ref "R194") (pin "1") (pinfunction "1_1") (pintype "passive"))
      (node (ref "U24") (pin "A22") (pinfunction "XO_A22") (pintype "passive"))
      (node (ref "Y2") (pin "3") (pinfunction "3_3") (pintype "passive"))
    )
    (net (code "80") (name "unconnected-(U24-GPIO0-PadA49)") (class "Default")
      (node (ref "U24") (pin "A49") (pinfunction "GPIO0_A49") (pintype "passive+no_connect"))
    )
    (net (code "81") (name "unconnected-(U24-GPIO1-PadB46)") (class "Default")
      (node (ref "U24") (pin "B46") (pinfunction "GPIO1_B46") (pintype "passive+no_connect"))
    )
    (net (code "82") (name "unconnected-(U24-GPIO2-PadB47)") (class "Default")
      (node (ref "U24") (pin "B47") (pinfunction "GPIO2_B47") (pintype "passive+no_connect"))
    )
    (net (code "83") (name "unconnected-(U24-GPIO3-PadB48)") (class "Default")
      (node (ref "U24") (pin "B48") (pinfunction "GPIO3_B48") (pintype "passive+no_connect"))
    )
    (net (code "84") (name "unconnected-(U24-NC-PadA14)") (class "Default")
      (node (ref "U24") (pin "A14") (pinfunction "NC_A14") (pintype "passive+no_connect"))
    )
    (net (code "85") (name "unconnected-(U24-NC-PadA26)") (class "Default")
      (node (ref "U24") (pin "A26") (pinfunction "NC_A26") (pintype "passive+no_connect"))
    )
    (net (code "86") (name "unconnected-(U24-NC-PadA43)") (class "Default")
      (node (ref "U24") (pin "A43") (pinfunction "NC_A43") (pintype "passive+no_connect"))
    )
    (net (code "87") (name "unconnected-(U24-NC-PadB8)") (class "Default")
      (node (ref "U24") (pin "B8") (pinfunction "NC_B8") (pintype "passive+no_connect"))
    )
    (net (code "88") (name "unconnected-(U24-NC-PadB13)") (class "Default")
      (node (ref "U24") (pin "B13") (pinfunction "NC_B13") (pintype "passive+no_connect"))
    )
    (net (code "89") (name "unconnected-(U24-NC-PadB29)") (class "Default")
      (node (ref "U24") (pin "B29") (pinfunction "NC_B29") (pintype "passive+no_connect"))
    )
  )
)
